# mcp23008-board.net
KiCad netlist of a schematic drawn in EAGLE
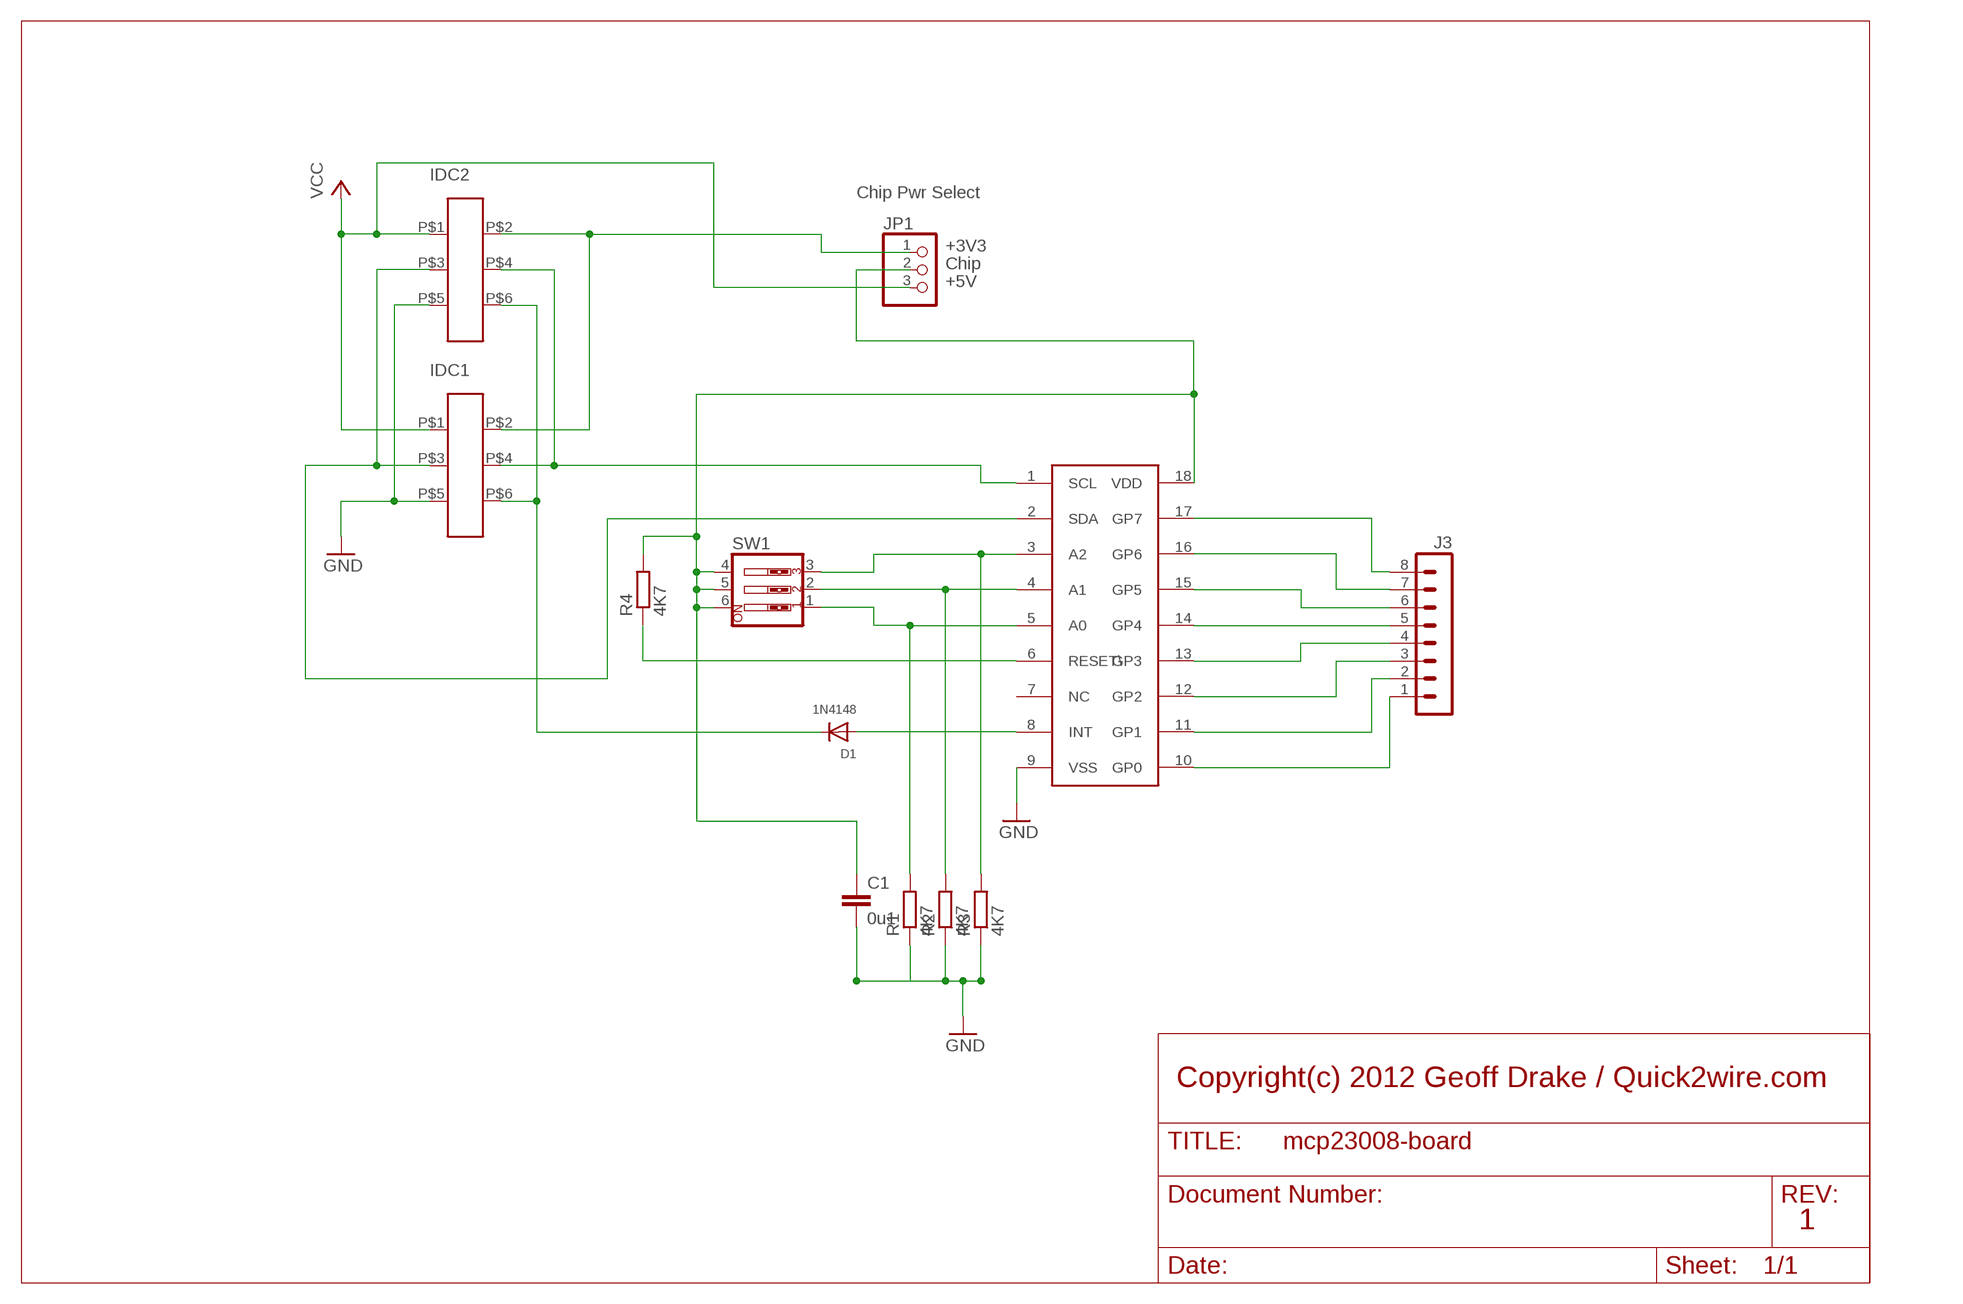
[diagram p0: schematic, sheet 1]

(export (version "E")
  (design (tool "Eeschema 10.0.6"))
  (components
    (comp (ref "C1")
      (value "0u1")
      (footprint "eagle-import:C025-030X050")
      (libsource (lib "eagle-import") (part "C-EU025-030X050"))
    )
    (comp (ref "D1")
      (value "1N4148")
      (footprint "eagle-import:DO-1N4148")
      (libsource (lib "eagle-import") (part "DIODEDO-1N4148"))
    )
    (comp (ref "IC1")
      (value "MCP23008")
      (footprint "eagle-import:DIL18")
      (libsource (lib "eagle-import") (part "MCP23008"))
    )
    (comp (ref "IDC1")
      (value "IDC-6W")
      (footprint "eagle-import:IDC-6W")
      (libsource (lib "eagle-import") (part "IDC-6W"))
    )
    (comp (ref "IDC2")
      (value "IDC-6W")
      (footprint "eagle-import:IDC-6W")
      (libsource (lib "eagle-import") (part "IDC-6W"))
    )
    (comp (ref "J3")
      (value "MA08-1")
      (footprint "eagle-import:MA08-1")
      (libsource (lib "eagle-import") (part "MA08-1"))
    )
    (comp (ref "JP1")
      (value "PINHD-1X3")
      (footprint "eagle-import:1X03")
      (libsource (lib "eagle-import") (part "PINHD-1X3"))
    )
    (comp (ref "R1")
      (value "4K7")
      (footprint "eagle-import:0207_10")
      (libsource (lib "eagle-import") (part "R-EU_0207/10"))
    )
    (comp (ref "R2")
      (value "4K7")
      (footprint "eagle-import:0207_10")
      (libsource (lib "eagle-import") (part "R-EU_0207/10"))
    )
    (comp (ref "R3")
      (value "4K7")
      (footprint "eagle-import:0207_10")
      (libsource (lib "eagle-import") (part "R-EU_0207/10"))
    )
    (comp (ref "R4")
      (value "4K7")
      (footprint "eagle-import:0207_10")
      (libsource (lib "eagle-import") (part "R-EU_0207/10"))
    )
    (comp (ref "SW1")
      (value "SW_DIP-3")
      (footprint "eagle-import:EDG-03")
      (libsource (lib "eagle-import") (part "SW_DIP-3"))
    )
  )
  (nets
    (net (code "1") (name "GND") (class "Default")
      (node (ref "C1") (pin "2") (pinfunction "2_2") (pintype "passive"))
      (node (ref "IC1") (pin "9") (pinfunction "VSS_9") (pintype "power_in"))
      (node (ref "IDC1") (pin "P$5") (pinfunction "P$5_P$5") (pintype "bidirectional"))
      (node (ref "IDC2") (pin "P$5") (pinfunction "P$5_P$5") (pintype "bidirectional"))
      (node (ref "R1") (pin "1") (pinfunction "1_1") (pintype "passive"))
      (node (ref "R2") (pin "1") (pinfunction "1_1") (pintype "passive"))
      (node (ref "R3") (pin "1") (pinfunction "1_1") (pintype "passive"))
    )
    (net (code "2") (name "Net-(D1-PadC)") (class "Default")
      (node (ref "D1") (pin "C") (pinfunction "C_C") (pintype "passive"))
      (node (ref "IDC1") (pin "P$6") (pinfunction "P$6_P$6") (pintype "bidirectional"))
      (node (ref "IDC2") (pin "P$6") (pinfunction "P$6_P$6") (pintype "bidirectional"))
    )
    (net (code "3") (name "Net-(IC1-A0)") (class "Default")
      (node (ref "IC1") (pin "5") (pinfunction "A0_5") (pintype "input"))
      (node (ref "R1") (pin "2") (pinfunction "2_2") (pintype "passive"))
      (node (ref "SW1") (pin "1") (pinfunction "1_1") (pintype "passive"))
    )
    (net (code "4") (name "Net-(IC1-A1)") (class "Default")
      (node (ref "IC1") (pin "4") (pinfunction "A1_4") (pintype "input"))
      (node (ref "R2") (pin "2") (pinfunction "2_2") (pintype "passive"))
      (node (ref "SW1") (pin "2") (pinfunction "2_2") (pintype "passive"))
    )
    (net (code "5") (name "Net-(IC1-A2)") (class "Default")
      (node (ref "IC1") (pin "3") (pinfunction "A2_3") (pintype "input"))
      (node (ref "R3") (pin "2") (pinfunction "2_2") (pintype "passive"))
      (node (ref "SW1") (pin "3") (pinfunction "3_3") (pintype "passive"))
    )
    (net (code "6") (name "Net-(IC1-GP0)") (class "Default")
      (node (ref "IC1") (pin "10") (pinfunction "GP0_10") (pintype "bidirectional"))
      (node (ref "J3") (pin "1") (pinfunction "1_1") (pintype "passive"))
    )
    (net (code "7") (name "Net-(IC1-GP1)") (class "Default")
      (node (ref "IC1") (pin "11") (pinfunction "GP1_11") (pintype "bidirectional"))
      (node (ref "J3") (pin "2") (pinfunction "2_2") (pintype "passive"))
    )
    (net (code "8") (name "Net-(IC1-GP2)") (class "Default")
      (node (ref "IC1") (pin "12") (pinfunction "GP2_12") (pintype "bidirectional"))
      (node (ref "J3") (pin "3") (pinfunction "3_3") (pintype "passive"))
    )
    (net (code "9") (name "Net-(IC1-GP3)") (class "Default")
      (node (ref "IC1") (pin "13") (pinfunction "GP3_13") (pintype "bidirectional"))
      (node (ref "J3") (pin "4") (pinfunction "4_4") (pintype "passive"))
    )
    (net (code "10") (name "Net-(IC1-GP4)") (class "Default")
      (node (ref "IC1") (pin "14") (pinfunction "GP4_14") (pintype "bidirectional"))
      (node (ref "J3") (pin "5") (pinfunction "5_5") (pintype "passive"))
    )
    (net (code "11") (name "Net-(IC1-GP5)") (class "Default")
      (node (ref "IC1") (pin "15") (pinfunction "GP5_15") (pintype "bidirectional"))
      (node (ref "J3") (pin "6") (pinfunction "6_6") (pintype "passive"))
    )
    (net (code "12") (name "Net-(IC1-GP6)") (class "Default")
      (node (ref "IC1") (pin "16") (pinfunction "GP6_16") (pintype "bidirectional"))
      (node (ref "J3") (pin "7") (pinfunction "7_7") (pintype "passive"))
    )
    (net (code "13") (name "Net-(IC1-GP7)") (class "Default")
      (node (ref "IC1") (pin "17") (pinfunction "GP7_17") (pintype "bidirectional"))
      (node (ref "J3") (pin "8") (pinfunction "8_8") (pintype "passive"))
    )
    (net (code "14") (name "Net-(IC1-INT)") (class "Default")
      (node (ref "D1") (pin "A") (pinfunction "A_A") (pintype "passive"))
      (node (ref "IC1") (pin "8") (pinfunction "INT_8") (pintype "output"))
    )
    (net (code "15") (name "Net-(IC1-RESET\\)") (class "Default")
      (node (ref "IC1") (pin "6") (pinfunction "RESET\\_6") (pintype "input"))
      (node (ref "R4") (pin "1") (pinfunction "1_1") (pintype "passive"))
    )
    (net (code "16") (name "Net-(IC1-SCL)") (class "Default")
      (node (ref "IC1") (pin "1") (pinfunction "SCL_1") (pintype "input"))
      (node (ref "IDC1") (pin "P$4") (pinfunction "P$4_P$4") (pintype "bidirectional"))
      (node (ref "IDC2") (pin "P$4") (pinfunction "P$4_P$4") (pintype "bidirectional"))
    )
    (net (code "17") (name "Net-(IC1-SDA)") (class "Default")
      (node (ref "IC1") (pin "2") (pinfunction "SDA_2") (pintype "bidirectional"))
      (node (ref "IDC1") (pin "P$3") (pinfunction "P$3_P$3") (pintype "bidirectional"))
      (node (ref "IDC2") (pin "P$3") (pinfunction "P$3_P$3") (pintype "bidirectional"))
    )
    (net (code "18") (name "Net-(IC1-VDD)") (class "Default")
      (node (ref "C1") (pin "1") (pinfunction "1_1") (pintype "passive"))
      (node (ref "IC1") (pin "18") (pinfunction "VDD_18") (pintype "power_in"))
      (node (ref "JP1") (pin "2") (pinfunction "2_2") (pintype "passive"))
      (node (ref "R4") (pin "2") (pinfunction "2_2") (pintype "passive"))
      (node (ref "SW1") (pin "4") (pinfunction "4_4") (pintype "passive"))
      (node (ref "SW1") (pin "5") (pinfunction "5_5") (pintype "passive"))
      (node (ref "SW1") (pin "6") (pinfunction "6_6") (pintype "passive"))
    )
    (net (code "19") (name "Net-(IDC1-PadP$2)") (class "Default")
      (node (ref "IDC1") (pin "P$2") (pinfunction "P$2_P$2") (pintype "bidirectional"))
      (node (ref "IDC2") (pin "P$2") (pinfunction "P$2_P$2") (pintype "bidirectional"))
      (node (ref "JP1") (pin "1") (pinfunction "1_1") (pintype "passive"))
    )
    (net (code "20") (name "VCC") (class "Default")
      (node (ref "IDC1") (pin "P$1") (pinfunction "P$1_P$1") (pintype "bidirectional"))
      (node (ref "IDC2") (pin "P$1") (pinfunction "P$1_P$1") (pintype "bidirectional"))
      (node (ref "JP1") (pin "3") (pinfunction "3_3") (pintype "passive"))
    )
    (net (code "21") (name "unconnected-(IC1-NC-Pad7)") (class "Default")
      (node (ref "IC1") (pin "7") (pinfunction "NC_7") (pintype "no_connect"))
    )
  )
)
